# 243-436_ESP32.net
KiCad netlist of a schematic drawn in Altium Designer
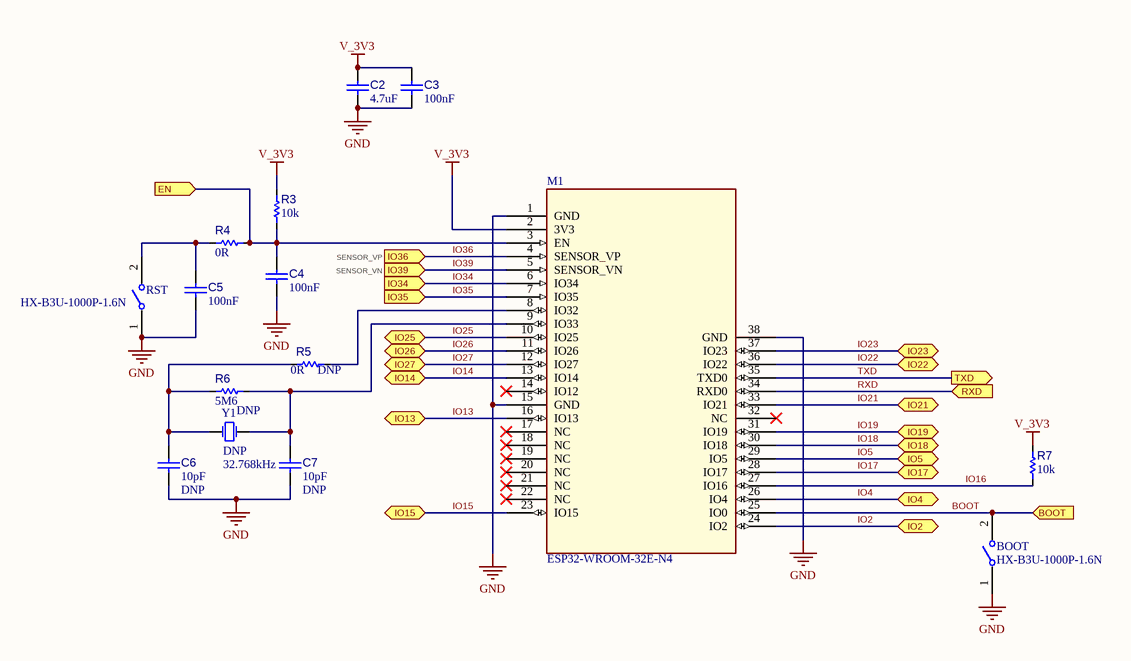
[diagram p0: 243-436_ESP32.SchDoc]

(export (version "E")
  (design (tool "Eeschema 10.0.6"))
  (components
    (comp (ref "BOOT")
      (value "HX-B3U-1000P-1.6N")
      (footprint "S_B3U-1000P")
      (description "SWITCH TACTILE SPST-NO 0.05A 12V")
      (libsource (lib "TEP-AltiumLib") (part "SW_B3U-1000P"))
    )
    (comp (ref "C2")
      (value "4.7uF")
      (footprint "C_1005[0402]")
      (description "Capacitor type 1")
      (fields (field (name "TOLERANCE") "20%") (field (name "Comment") "CAP CER 4.7uF 6.3V X5R 0402"))
      (libsource (lib "TEP_243-Altium_DBLib") (part "capacitor"))
    )
    (comp (ref "C3")
      (value "100nF")
      (footprint "C_1005[0402]")
      (description "Capacitor type 1")
      (fields (field (name "TOLERANCE") "10%") (field (name "Comment") "CAP CER 100nF 50V 0402"))
      (libsource (lib "TEP_243-Altium_DBLib") (part "capacitor"))
    )
    (comp (ref "C4")
      (value "100nF")
      (footprint "C_1005[0402]")
      (description "Capacitor type 1")
      (fields (field (name "TOLERANCE") "10%") (field (name "Comment") "DNP"))
      (libsource (lib "TEP_243-Altium_DBLib") (part "capacitor"))
    )
    (comp (ref "C5")
      (value "100nF")
      (footprint "C_1005[0402]")
      (description "Capacitor type 1")
      (fields (field (name "TOLERANCE") "10%") (field (name "Comment") "CAP CER 100nF 50V 0402"))
      (libsource (lib "TEP_243-Altium_DBLib") (part "capacitor"))
    )
    (comp (ref "C6")
      (value "DNP")
      (footprint "C_1005[0402]")
      (description "Capacitor type 1")
      (fields (field (name "ALTIUM_VALUE") "10pF") (field (name "TOLERANCE") "5%"))
      (libsource (lib "TEP_243-Altium_DBLib") (part "capacitor"))
    )
    (comp (ref "C7")
      (value "DNP")
      (footprint "C_1005[0402]")
      (description "Capacitor type 1")
      (fields (field (name "ALTIUM_VALUE") "10pF") (field (name "TOLERANCE") "5%"))
      (libsource (lib "TEP_243-Altium_DBLib") (part "capacitor"))
    )
    (comp (ref "M1")
      (value "ESP32-WROOM-32E-N4")
      (footprint "ESP32­WROOM­32E_EXP-TH")
      (description "ESP32 Module SMT Castellated")
      (libsource (lib "TEP-AltiumLib-Modules") (part "M_ESP32-WROOM-32E-N4-TH"))
    )
    (comp (ref "R3")
      (value "10k")
      (footprint "R_1005[0402]")
      (description "Resistor type 1")
      (fields (field (name "TOLERANCE") "1%") (field (name "Comment") "DNP"))
      (libsource (lib "TEP_243-Altium_DBLib") (part "resistor"))
    )
    (comp (ref "R4")
      (value "0R")
      (footprint "R_1005[0402]")
      (description "Resistor type 1")
      (fields (field (name "Comment") "Res 0R 0402"))
      (libsource (lib "TEP_243-Altium_DBLib") (part "resistor"))
    )
    (comp (ref "R5")
      (value "DNP")
      (footprint "R_1005[0402]")
      (description "Resistor type 1")
      (fields (field (name "ALTIUM_VALUE") "0R"))
      (libsource (lib "TEP_243-Altium_DBLib") (part "resistor"))
    )
    (comp (ref "R6")
      (value "DNP")
      (footprint "R_1005[0402]")
      (description "Resistor type 1")
      (fields (field (name "ALTIUM_VALUE") "5M6") (field (name "TOLERANCE") "1%"))
      (libsource (lib "TEP_243-Altium_DBLib") (part "resistor"))
    )
    (comp (ref "R7")
      (value "10k")
      (footprint "R_1005[0402]")
      (description "Resistor type 1")
      (fields (field (name "TOLERANCE") "1%") (field (name "Comment") "Res 10k 1% 0402"))
      (libsource (lib "TEP_243-Altium_DBLib") (part "resistor"))
    )
    (comp (ref "RST")
      (value "HX-B3U-1000P-1.6N")
      (footprint "S_B3U-1000P")
      (description "SWITCH TACTILE SPST-NO 0.05A 12V")
      (libsource (lib "TEP-AltiumLib") (part "SW_B3U-1000P"))
    )
    (comp (ref "Y1")
      (value "DNP")
      (footprint "Y_2012_2P")
      (description "Crystal NDK 2.0x1.2mm  32.768 KHz")
      (fields (field (name "ALTIUM_VALUE") "32.768kHz"))
      (libsource (lib "TEP-AltiumLib") (part "Y_NX2012_32K768"))
    )
  )
  (nets
    (net (code "1") (name "/BOOT") (class "Default")
      (node (ref "BOOT") (pin "2") (pinfunction "2_2") (pintype "passive"))
      (node (ref "M1") (pin "25") (pinfunction "IO0_25") (pintype "bidirectional"))
    )
    (net (code "2") (name "/EN") (class "Default")
      (node (ref "C4") (pin "2") (pinfunction "2_2") (pintype "passive"))
      (node (ref "M1") (pin "3") (pinfunction "EN_3") (pintype "input"))
      (node (ref "R3") (pin "1") (pinfunction "1_1") (pintype "passive"))
      (node (ref "R4") (pin "2") (pinfunction "2_2") (pintype "passive"))
    )
    (net (code "3") (name "/IO2") (class "Default")
      (node (ref "M1") (pin "24") (pinfunction "IO2_24") (pintype "bidirectional"))
    )
    (net (code "4") (name "/IO4") (class "Default")
      (node (ref "M1") (pin "26") (pinfunction "IO4_26") (pintype "bidirectional"))
    )
    (net (code "5") (name "/IO5") (class "Default")
      (node (ref "M1") (pin "29") (pinfunction "IO5_29") (pintype "bidirectional"))
    )
    (net (code "6") (name "/IO13") (class "Default")
      (node (ref "M1") (pin "16") (pinfunction "IO13_16") (pintype "bidirectional"))
    )
    (net (code "7") (name "/IO14") (class "Default")
      (node (ref "M1") (pin "13") (pinfunction "IO14_13") (pintype "bidirectional"))
    )
    (net (code "8") (name "/IO15") (class "Default")
      (node (ref "M1") (pin "23") (pinfunction "IO15_23") (pintype "bidirectional"))
    )
    (net (code "9") (name "/IO16") (class "Default")
      (node (ref "M1") (pin "27") (pinfunction "IO16_27") (pintype "bidirectional"))
      (node (ref "R7") (pin "1") (pinfunction "1_1") (pintype "passive"))
    )
    (net (code "10") (name "/IO17") (class "Default")
      (node (ref "M1") (pin "28") (pinfunction "IO17_28") (pintype "bidirectional"))
    )
    (net (code "11") (name "/IO18") (class "Default")
      (node (ref "M1") (pin "30") (pinfunction "IO18_30") (pintype "bidirectional"))
    )
    (net (code "12") (name "/IO19") (class "Default")
      (node (ref "M1") (pin "31") (pinfunction "IO19_31") (pintype "bidirectional"))
    )
    (net (code "13") (name "/IO21") (class "Default")
      (node (ref "M1") (pin "33") (pinfunction "IO21_33") (pintype "bidirectional"))
    )
    (net (code "14") (name "/IO22") (class "Default")
      (node (ref "M1") (pin "36") (pinfunction "IO22_36") (pintype "bidirectional"))
    )
    (net (code "15") (name "/IO23") (class "Default")
      (node (ref "M1") (pin "37") (pinfunction "IO23_37") (pintype "bidirectional"))
    )
    (net (code "16") (name "/IO25") (class "Default")
      (node (ref "M1") (pin "10") (pinfunction "IO25_10") (pintype "bidirectional"))
    )
    (net (code "17") (name "/IO26") (class "Default")
      (node (ref "M1") (pin "11") (pinfunction "IO26_11") (pintype "bidirectional"))
    )
    (net (code "18") (name "/IO27") (class "Default")
      (node (ref "M1") (pin "12") (pinfunction "IO27_12") (pintype "bidirectional"))
    )
    (net (code "19") (name "/IO34") (class "Default")
      (node (ref "M1") (pin "6") (pinfunction "IO34_6") (pintype "input"))
    )
    (net (code "20") (name "/IO35") (class "Default")
      (node (ref "M1") (pin "7") (pinfunction "IO35_7") (pintype "input"))
    )
    (net (code "21") (name "/IO36") (class "Default")
      (node (ref "M1") (pin "4") (pinfunction "SENSOR_VP_4") (pintype "input"))
    )
    (net (code "22") (name "/IO39") (class "Default")
      (node (ref "M1") (pin "5") (pinfunction "SENSOR_VN_5") (pintype "input"))
    )
    (net (code "23") (name "/RXD") (class "Default")
      (node (ref "M1") (pin "34") (pinfunction "RXD0_34") (pintype "bidirectional"))
    )
    (net (code "24") (name "/TXD") (class "Default")
      (node (ref "M1") (pin "35") (pinfunction "TXD0_35") (pintype "bidirectional"))
    )
    (net (code "25") (name "GND") (class "Default")
      (node (ref "BOOT") (pin "1") (pinfunction "1_1") (pintype "passive"))
      (node (ref "C2") (pin "1") (pinfunction "1_1") (pintype "passive"))
      (node (ref "C3") (pin "1") (pinfunction "1_1") (pintype "passive"))
      (node (ref "C4") (pin "1") (pinfunction "1_1") (pintype "passive"))
      (node (ref "C5") (pin "1") (pinfunction "1_1") (pintype "passive"))
      (node (ref "C6") (pin "1") (pinfunction "1_1") (pintype "passive"))
      (node (ref "C7") (pin "1") (pinfunction "1_1") (pintype "passive"))
      (node (ref "M1") (pin "1") (pinfunction "GND_1") (pintype "power_in"))
      (node (ref "M1") (pin "15") (pinfunction "GND_15") (pintype "power_in"))
      (node (ref "M1") (pin "38") (pinfunction "GND_38") (pintype "power_in"))
      (node (ref "RST") (pin "1") (pinfunction "1_1") (pintype "passive"))
    )
    (net (code "26") (name "Net-(C5-Pad2)") (class "Default")
      (node (ref "C5") (pin "2") (pinfunction "2_2") (pintype "passive"))
      (node (ref "R4") (pin "1") (pinfunction "1_1") (pintype "passive"))
      (node (ref "RST") (pin "2") (pinfunction "2_2") (pintype "passive"))
    )
    (net (code "27") (name "Net-(M1-IO32)") (class "Default")
      (node (ref "M1") (pin "8") (pinfunction "IO32_8") (pintype "bidirectional"))
      (node (ref "R5") (pin "2") (pinfunction "2_2") (pintype "passive"))
    )
    (net (code "28") (name "Net-(M1-IO33)") (class "Default")
      (node (ref "C7") (pin "2") (pinfunction "2_2") (pintype "passive"))
      (node (ref "M1") (pin "9") (pinfunction "IO33_9") (pintype "bidirectional"))
      (node (ref "R6") (pin "2") (pinfunction "2_2") (pintype "passive"))
      (node (ref "Y1") (pin "2") (pinfunction "OSC2_2") (pintype "passive"))
    )
    (net (code "29") (name "Net-(Y1-OSC1)") (class "Default")
      (node (ref "C6") (pin "2") (pinfunction "2_2") (pintype "passive"))
      (node (ref "R5") (pin "1") (pinfunction "1_1") (pintype "passive"))
      (node (ref "R6") (pin "1") (pinfunction "1_1") (pintype "passive"))
      (node (ref "Y1") (pin "1") (pinfunction "OSC1_1") (pintype "passive"))
    )
    (net (code "30") (name "V_3V3") (class "Default")
      (node (ref "C2") (pin "2") (pinfunction "2_2") (pintype "passive"))
      (node (ref "C3") (pin "2") (pinfunction "2_2") (pintype "passive"))
      (node (ref "M1") (pin "2") (pinfunction "3V3_2") (pintype "power_in"))
      (node (ref "R3") (pin "2") (pinfunction "2_2") (pintype "passive"))
      (node (ref "R7") (pin "2") (pinfunction "2_2") (pintype "passive"))
    )
    (net (code "31") (name "unconnected-(M1-IO12-Pad14)") (class "Default")
      (node (ref "M1") (pin "14") (pinfunction "IO12_14") (pintype "bidirectional+no_connect"))
    )
    (net (code "32") (name "unconnected-(M1-NC-Pad17)") (class "Default")
      (node (ref "M1") (pin "17") (pinfunction "NC_17") (pintype "passive+no_connect"))
    )
    (net (code "33") (name "unconnected-(M1-NC-Pad18)") (class "Default")
      (node (ref "M1") (pin "18") (pinfunction "NC_18") (pintype "passive+no_connect"))
    )
    (net (code "34") (name "unconnected-(M1-NC-Pad19)") (class "Default")
      (node (ref "M1") (pin "19") (pinfunction "NC_19") (pintype "passive+no_connect"))
    )
    (net (code "35") (name "unconnected-(M1-NC-Pad20)") (class "Default")
      (node (ref "M1") (pin "20") (pinfunction "NC_20") (pintype "passive+no_connect"))
    )
    (net (code "36") (name "unconnected-(M1-NC-Pad21)") (class "Default")
      (node (ref "M1") (pin "21") (pinfunction "NC_21") (pintype "passive+no_connect"))
    )
    (net (code "37") (name "unconnected-(M1-NC-Pad22)") (class "Default")
      (node (ref "M1") (pin "22") (pinfunction "NC_22") (pintype "passive+no_connect"))
    )
    (net (code "38") (name "unconnected-(M1-NC-Pad32)") (class "Default")
      (node (ref "M1") (pin "32") (pinfunction "NC_32") (pintype "passive+no_connect"))
    )
  )
)
